# gaggia.net
KiCad netlist of a schematic drawn in EAGLE
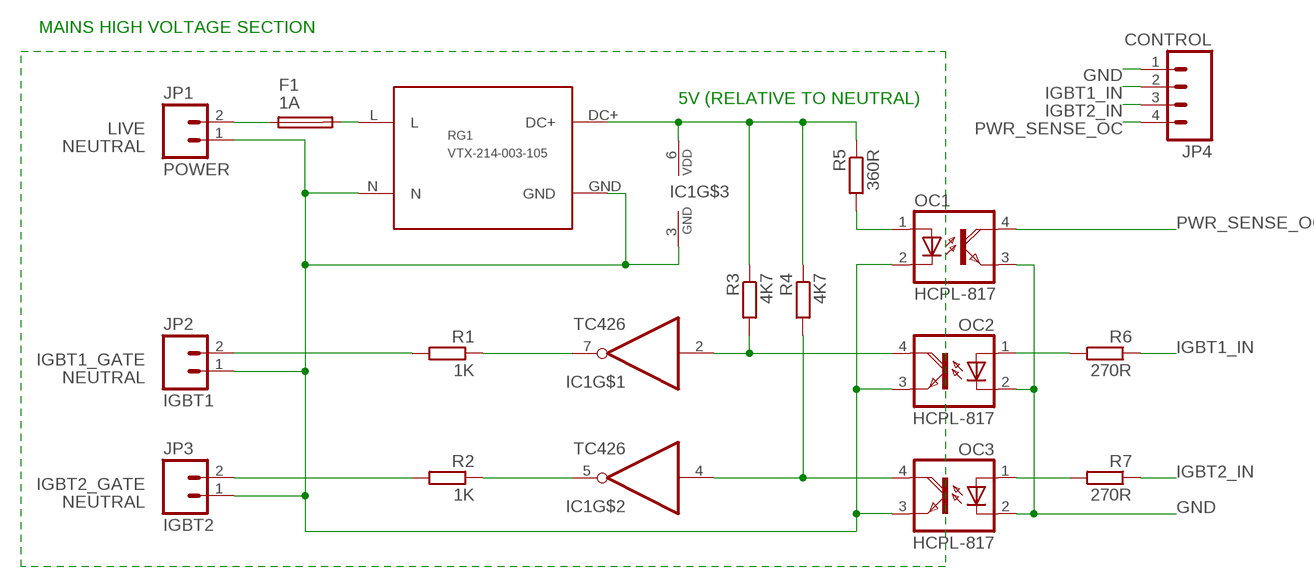
[diagram p0: schematic, sheet 1]

(export (version "E")
  (design (tool "Eeschema 10.0.6"))
  (components
    (comp (ref "F1")
      (value "1A")
      (footprint "eagle-import:TE5")
      (libsource (lib "eagle-import") (part "FUSETE5"))
    )
    (comp (ref "IC1")
      (value "TC426")
      (footprint "eagle-import:DIL08")
      (libsource (lib "eagle-import") (part "TC426"))
    )
    (comp (ref "JP1")
      (value "POWER")
      (footprint "eagle-import:SCREWTERMINAL-5MM-2")
      (libsource (lib "eagle-import") (part "M025MM"))
    )
    (comp (ref "JP2")
      (value "IGBT1")
      (footprint "eagle-import:1X02")
      (libsource (lib "eagle-import") (part "M02PTH"))
    )
    (comp (ref "JP3")
      (value "IGBT2")
      (footprint "eagle-import:1X02")
      (libsource (lib "eagle-import") (part "M02PTH"))
    )
    (comp (ref "JP4")
      (value "CONTROL")
      (footprint "eagle-import:1X04")
      (libsource (lib "eagle-import") (part "M04PTH"))
    )
    (comp (ref "OC1")
      (value "HCPL-817")
      (footprint "eagle-import:DIL04")
      (libsource (lib "eagle-import") (part "TIL197"))
    )
    (comp (ref "OC2")
      (value "HCPL-817")
      (footprint "eagle-import:DIL04")
      (libsource (lib "eagle-import") (part "TIL197"))
    )
    (comp (ref "OC3")
      (value "HCPL-817")
      (footprint "eagle-import:DIL04")
      (libsource (lib "eagle-import") (part "TIL197"))
    )
    (comp (ref "R1")
      (value "1K")
      (footprint "eagle-import:0204_7")
      (libsource (lib "eagle-import") (part "R-EU_0204/7"))
    )
    (comp (ref "R2")
      (value "1K")
      (footprint "eagle-import:0204_7")
      (libsource (lib "eagle-import") (part "R-EU_0204/7"))
    )
    (comp (ref "R3")
      (value "4K7")
      (footprint "eagle-import:0204_7")
      (libsource (lib "eagle-import") (part "R-EU_0204/7"))
    )
    (comp (ref "R4")
      (value "4K7")
      (footprint "eagle-import:0204_7")
      (libsource (lib "eagle-import") (part "R-EU_0204/7"))
    )
    (comp (ref "R5")
      (value "360R")
      (footprint "eagle-import:0204_7")
      (libsource (lib "eagle-import") (part "R-EU_0204/7"))
    )
    (comp (ref "R6")
      (value "270R")
      (footprint "eagle-import:0204_7")
      (libsource (lib "eagle-import") (part "R-EU_0204/7"))
    )
    (comp (ref "R7")
      (value "270R")
      (footprint "eagle-import:0204_7")
      (libsource (lib "eagle-import") (part "R-EU_0204/7"))
    )
    (comp (ref "RG1")
      (value "VTX-214-003-105")
      (footprint "eagle-import:VTX-214-003")
      (libsource (lib "eagle-import") (part "VTX-214-003-105"))
    )
  )
  (nets
    (net (code "1") (name "/GND") (class "Default")
      (node (ref "JP4") (pin "1") (pinfunction "1_1") (pintype "passive"))
      (node (ref "OC1") (pin "3") (pinfunction "EMI_3") (pintype "passive"))
      (node (ref "OC2") (pin "2") (pinfunction "C_2") (pintype "passive"))
      (node (ref "OC3") (pin "2") (pinfunction "C_2") (pintype "passive"))
    )
    (net (code "2") (name "/IGBT1_GATE") (class "Default")
      (node (ref "JP2") (pin "2") (pinfunction "2_2") (pintype "passive"))
      (node (ref "R1") (pin "2") (pinfunction "2_2") (pintype "passive"))
    )
    (net (code "3") (name "/IGBT1_IN") (class "Default")
      (node (ref "JP4") (pin "2") (pinfunction "2_2") (pintype "passive"))
      (node (ref "R6") (pin "1") (pinfunction "1_1") (pintype "passive"))
    )
    (net (code "4") (name "/IGBT2_GATE") (class "Default")
      (node (ref "JP3") (pin "2") (pinfunction "2_2") (pintype "passive"))
      (node (ref "R2") (pin "2") (pinfunction "2_2") (pintype "passive"))
    )
    (net (code "5") (name "/IGBT2_IN") (class "Default")
      (node (ref "JP4") (pin "3") (pinfunction "3_3") (pintype "passive"))
      (node (ref "R7") (pin "1") (pinfunction "1_1") (pintype "passive"))
    )
    (net (code "6") (name "/LIVE") (class "Default")
      (node (ref "F1") (pin "1") (pinfunction "1_1") (pintype "passive"))
      (node (ref "JP1") (pin "2") (pinfunction "2_2") (pintype "passive"))
    )
    (net (code "7") (name "/NEUTRAL") (class "Default")
      (node (ref "IC1") (pin "3") (pinfunction "GND_3") (pintype "power_in"))
      (node (ref "JP1") (pin "1") (pinfunction "1_1") (pintype "passive"))
      (node (ref "JP2") (pin "1") (pinfunction "1_1") (pintype "passive"))
      (node (ref "JP3") (pin "1") (pinfunction "1_1") (pintype "passive"))
      (node (ref "OC1") (pin "2") (pinfunction "C_2") (pintype "passive"))
      (node (ref "OC2") (pin "3") (pinfunction "EMI_3") (pintype "passive"))
      (node (ref "OC3") (pin "3") (pinfunction "EMI_3") (pintype "passive"))
      (node (ref "RG1") (pin "GND") (pinfunction "GND_GND") (pintype "power_in"))
      (node (ref "RG1") (pin "N") (pinfunction "N_N") (pintype "power_in"))
    )
    (net (code "8") (name "/PWR_SENSE_OC") (class "Default")
      (node (ref "JP4") (pin "4") (pinfunction "4_4") (pintype "passive"))
      (node (ref "OC1") (pin "4") (pinfunction "COL_4") (pintype "passive"))
    )
    (net (code "9") (name "Net-(F1-Pad2)") (class "Default")
      (node (ref "F1") (pin "2") (pinfunction "2_2") (pintype "passive"))
      (node (ref "RG1") (pin "L") (pinfunction "L_L") (pintype "power_in"))
    )
    (net (code "10") (name "Net-(IC1A-I)") (class "Default")
      (node (ref "IC1") (pin "2") (pinfunction "I_2") (pintype "input"))
      (node (ref "OC2") (pin "4") (pinfunction "COL_4") (pintype "passive"))
      (node (ref "R3") (pin "2") (pinfunction "2_2") (pintype "passive"))
    )
    (net (code "11") (name "Net-(IC1A-O)") (class "Default")
      (node (ref "IC1") (pin "7") (pinfunction "O_7") (pintype "output"))
      (node (ref "R1") (pin "1") (pinfunction "1_1") (pintype "passive"))
    )
    (net (code "12") (name "Net-(IC1B-I)") (class "Default")
      (node (ref "IC1") (pin "4") (pinfunction "I_4") (pintype "input"))
      (node (ref "OC3") (pin "4") (pinfunction "COL_4") (pintype "passive"))
      (node (ref "R4") (pin "2") (pinfunction "2_2") (pintype "passive"))
    )
    (net (code "13") (name "Net-(IC1B-O)") (class "Default")
      (node (ref "IC1") (pin "5") (pinfunction "O_5") (pintype "output"))
      (node (ref "R2") (pin "1") (pinfunction "1_1") (pintype "passive"))
    )
    (net (code "14") (name "Net-(IC1C-VDD)") (class "Default")
      (node (ref "IC1") (pin "6") (pinfunction "VDD_6") (pintype "power_in"))
      (node (ref "R3") (pin "1") (pinfunction "1_1") (pintype "passive"))
      (node (ref "R4") (pin "1") (pinfunction "1_1") (pintype "passive"))
      (node (ref "R5") (pin "1") (pinfunction "1_1") (pintype "passive"))
      (node (ref "RG1") (pin "DC+") (pinfunction "DC+_DC+") (pintype "power_in"))
    )
    (net (code "15") (name "Net-(OC1-A)") (class "Default")
      (node (ref "OC1") (pin "1") (pinfunction "A_1") (pintype "passive"))
      (node (ref "R5") (pin "2") (pinfunction "2_2") (pintype "passive"))
    )
    (net (code "16") (name "Net-(OC2-A)") (class "Default")
      (node (ref "OC2") (pin "1") (pinfunction "A_1") (pintype "passive"))
      (node (ref "R6") (pin "2") (pinfunction "2_2") (pintype "passive"))
    )
    (net (code "17") (name "Net-(OC3-A)") (class "Default")
      (node (ref "OC3") (pin "1") (pinfunction "A_1") (pintype "passive"))
      (node (ref "R7") (pin "2") (pinfunction "2_2") (pintype "passive"))
    )
  )
)
